# Potentiometers.net
KiCad netlist of a schematic drawn in Altium Designer
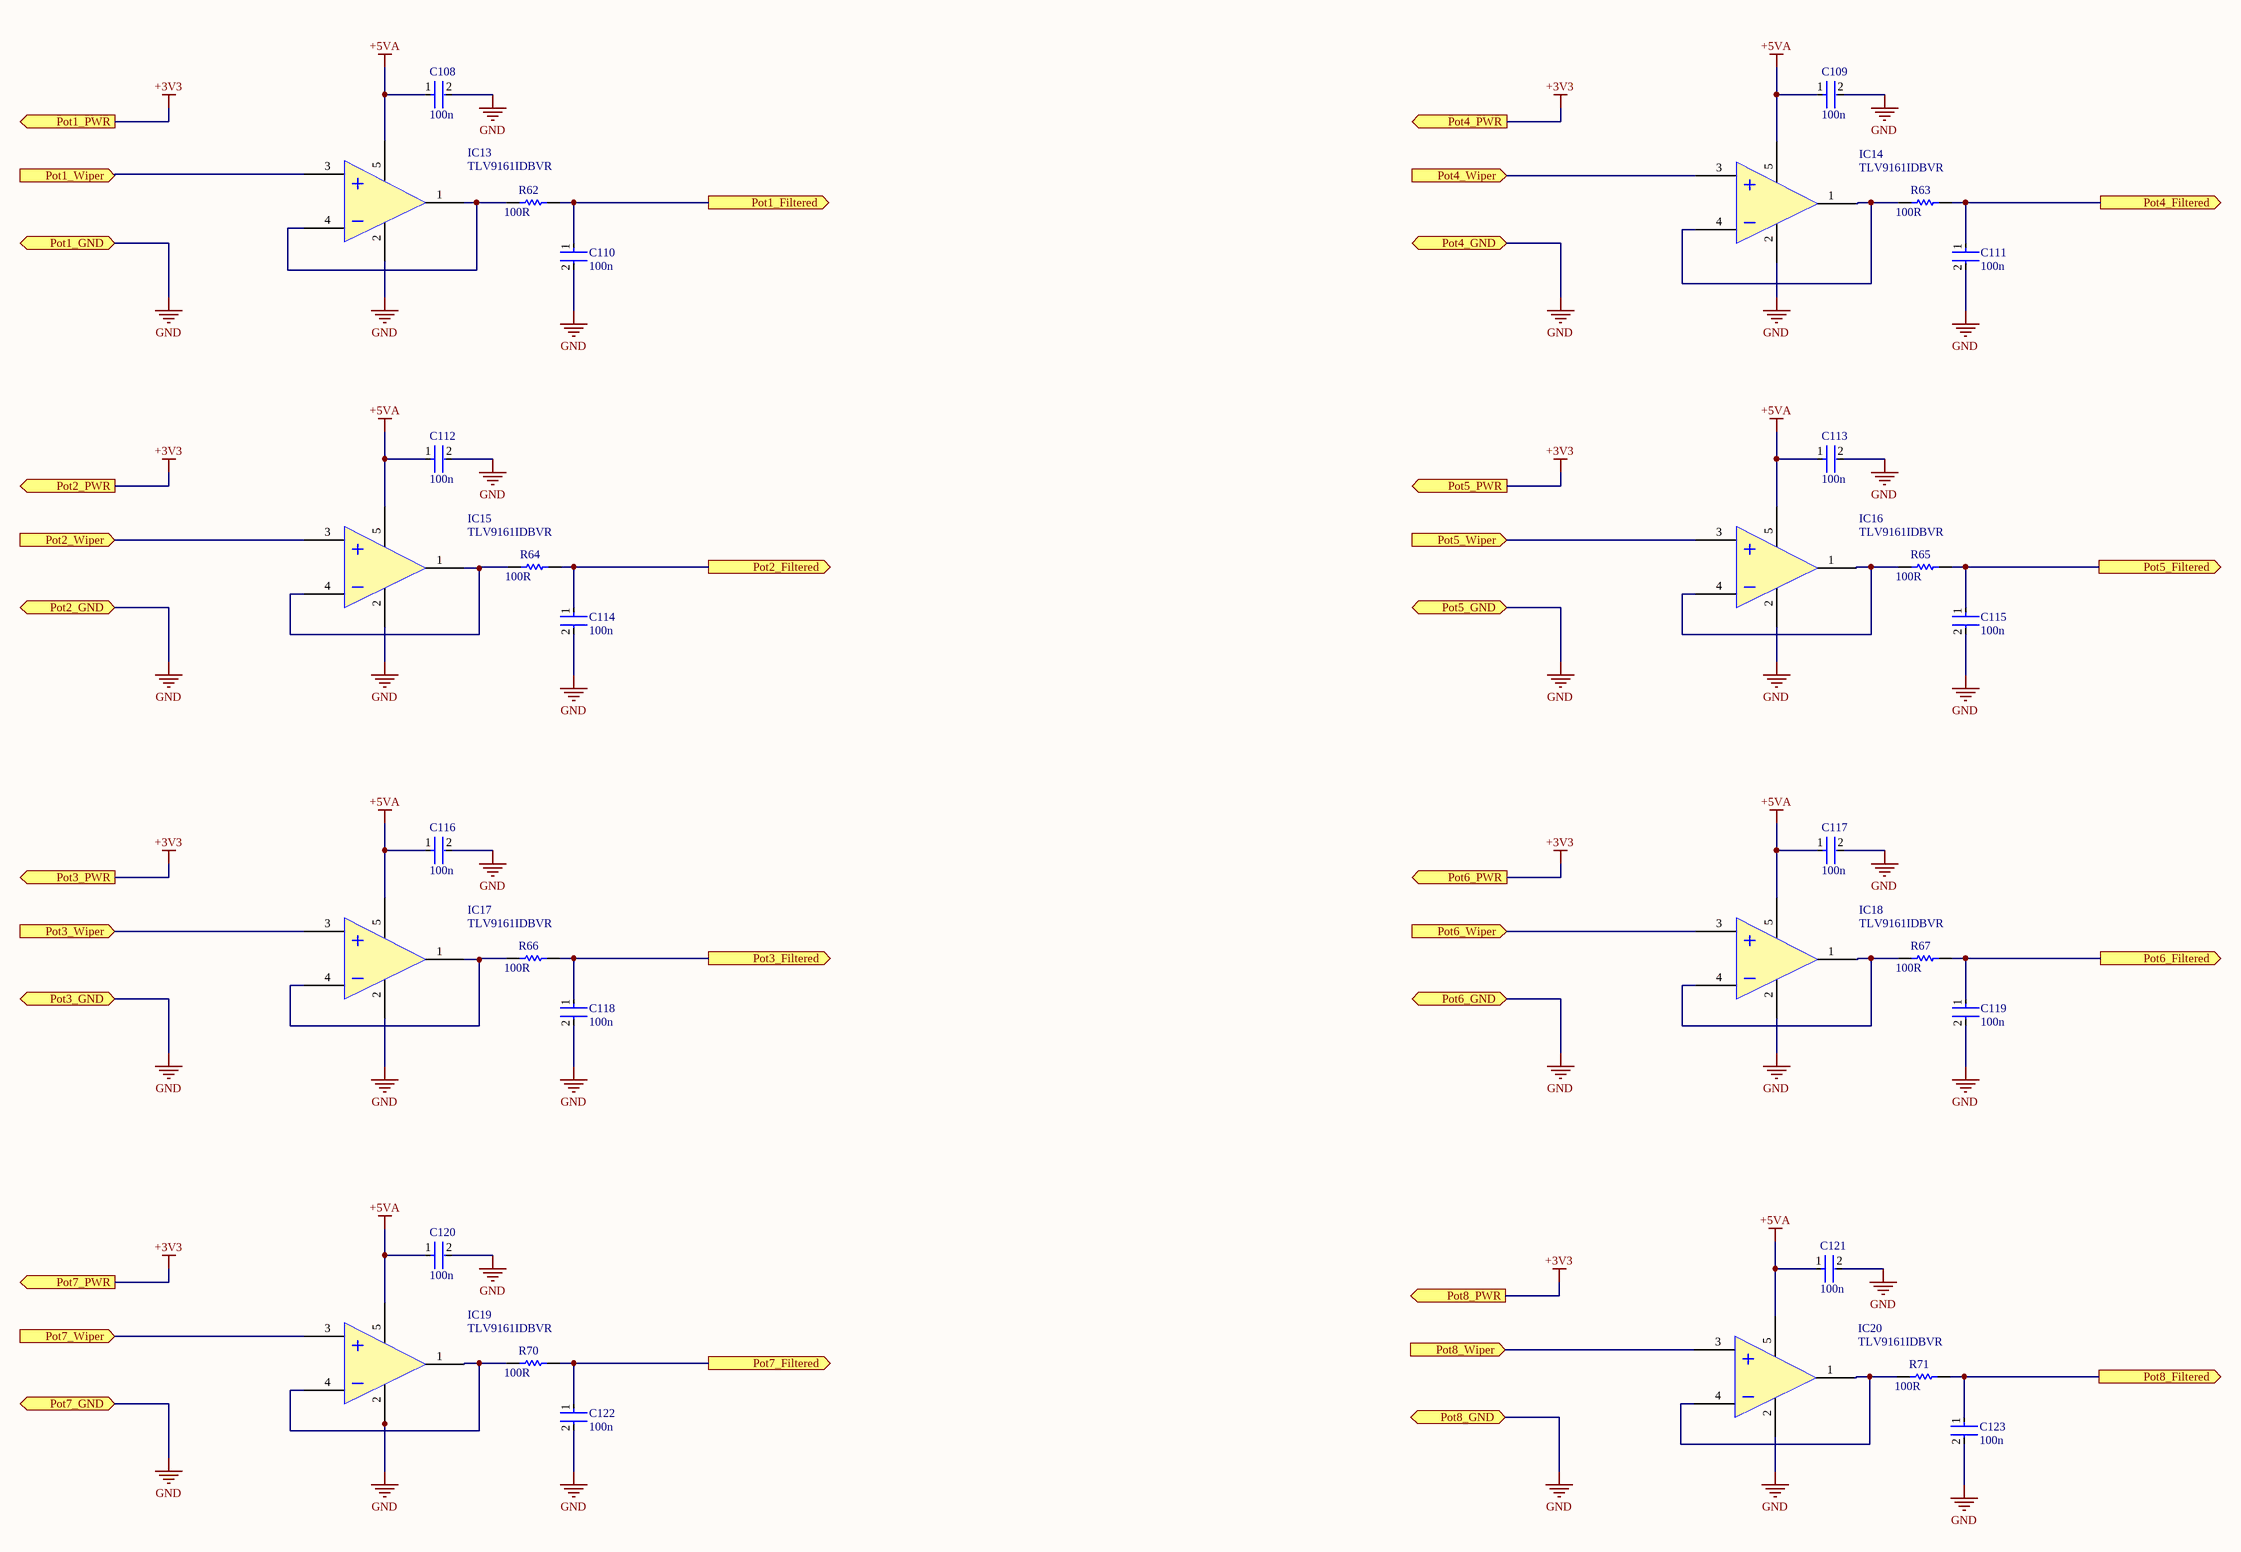
[diagram p0: Potentiometers.SchDoc]

(export (version "E")
  (design (tool "Eeschema 10.0.6"))
  (components
    (comp (ref "C108")
      (value "GCM155R71H104ME02J")
      (footprint "FP-GCM155-0_05-IPC_A")
      (description "Ceramic Capacitor for Automotive 100nF ±20% 50VDC X7R 0402 Paper T/R")
      (fields (field (name "CAPACITANCE") "100n"))
      (libsource (lib "Altium Content Vault") (part "02cd4be3c70576c341d710602a673aa"))
    )
    (comp (ref "C109")
      (value "GCM155R71H104ME02J")
      (footprint "FP-GCM155-0_05-IPC_A")
      (description "Ceramic Capacitor for Automotive 100nF ±20% 50VDC X7R 0402 Paper T/R")
      (fields (field (name "CAPACITANCE") "100n"))
      (libsource (lib "Altium Content Vault") (part "02cd4be3c70576c341d710602a673aa"))
    )
    (comp (ref "C110")
      (value "GCM155R71H104ME02J")
      (footprint "FP-GCM155-0_05-IPC_A")
      (description "Ceramic Capacitor for Automotive 100nF ±20% 50VDC X7R 0402 Paper T/R")
      (fields (field (name "CAPACITANCE") "100n"))
      (libsource (lib "Altium Content Vault") (part "02cd4be3c70576c341d710602a673aa"))
    )
    (comp (ref "C111")
      (value "GCM155R71H104ME02J")
      (footprint "FP-GCM155-0_05-IPC_A")
      (description "Ceramic Capacitor for Automotive 100nF ±20% 50VDC X7R 0402 Paper T/R")
      (fields (field (name "CAPACITANCE") "100n"))
      (libsource (lib "Altium Content Vault") (part "02cd4be3c70576c341d710602a673aa"))
    )
    (comp (ref "C112")
      (value "GCM155R71H104ME02J")
      (footprint "FP-GCM155-0_05-IPC_A")
      (description "Ceramic Capacitor for Automotive 100nF ±20% 50VDC X7R 0402 Paper T/R")
      (fields (field (name "CAPACITANCE") "100n"))
      (libsource (lib "Altium Content Vault") (part "02cd4be3c70576c341d710602a673aa"))
    )
    (comp (ref "C113")
      (value "GCM155R71H104ME02J")
      (footprint "FP-GCM155-0_05-IPC_A")
      (description "Ceramic Capacitor for Automotive 100nF ±20% 50VDC X7R 0402 Paper T/R")
      (fields (field (name "CAPACITANCE") "100n"))
      (libsource (lib "Altium Content Vault") (part "02cd4be3c70576c341d710602a673aa"))
    )
    (comp (ref "C114")
      (value "GCM155R71H104ME02J")
      (footprint "FP-GCM155-0_05-IPC_A")
      (description "Ceramic Capacitor for Automotive 100nF ±20% 50VDC X7R 0402 Paper T/R")
      (fields (field (name "CAPACITANCE") "100n"))
      (libsource (lib "Altium Content Vault") (part "02cd4be3c70576c341d710602a673aa"))
    )
    (comp (ref "C115")
      (value "GCM155R71H104ME02J")
      (footprint "FP-GCM155-0_05-IPC_A")
      (description "Ceramic Capacitor for Automotive 100nF ±20% 50VDC X7R 0402 Paper T/R")
      (fields (field (name "CAPACITANCE") "100n"))
      (libsource (lib "Altium Content Vault") (part "02cd4be3c70576c341d710602a673aa"))
    )
    (comp (ref "C116")
      (value "GCM155R71H104ME02J")
      (footprint "FP-GCM155-0_05-IPC_A")
      (description "Ceramic Capacitor for Automotive 100nF ±20% 50VDC X7R 0402 Paper T/R")
      (fields (field (name "CAPACITANCE") "100n"))
      (libsource (lib "Altium Content Vault") (part "02cd4be3c70576c341d710602a673aa"))
    )
    (comp (ref "C117")
      (value "GCM155R71H104ME02J")
      (footprint "FP-GCM155-0_05-IPC_A")
      (description "Ceramic Capacitor for Automotive 100nF ±20% 50VDC X7R 0402 Paper T/R")
      (fields (field (name "CAPACITANCE") "100n"))
      (libsource (lib "Altium Content Vault") (part "02cd4be3c70576c341d710602a673aa"))
    )
    (comp (ref "C118")
      (value "GCM155R71H104ME02J")
      (footprint "FP-GCM155-0_05-IPC_A")
      (description "Ceramic Capacitor for Automotive 100nF ±20% 50VDC X7R 0402 Paper T/R")
      (fields (field (name "CAPACITANCE") "100n"))
      (libsource (lib "Altium Content Vault") (part "02cd4be3c70576c341d710602a673aa"))
    )
    (comp (ref "C119")
      (value "GCM155R71H104ME02J")
      (footprint "FP-GCM155-0_05-IPC_A")
      (description "Ceramic Capacitor for Automotive 100nF ±20% 50VDC X7R 0402 Paper T/R")
      (fields (field (name "CAPACITANCE") "100n"))
      (libsource (lib "Altium Content Vault") (part "02cd4be3c70576c341d710602a673aa"))
    )
    (comp (ref "C120")
      (value "GCM155R71H104ME02J")
      (footprint "FP-GCM155-0_05-IPC_A")
      (description "Ceramic Capacitor for Automotive 100nF ±20% 50VDC X7R 0402 Paper T/R")
      (fields (field (name "CAPACITANCE") "100n"))
      (libsource (lib "Altium Content Vault") (part "02cd4be3c70576c341d710602a673aa"))
    )
    (comp (ref "C121")
      (value "GCM155R71H104ME02J")
      (footprint "FP-GCM155-0_05-IPC_A")
      (description "Ceramic Capacitor for Automotive 100nF ±20% 50VDC X7R 0402 Paper T/R")
      (fields (field (name "CAPACITANCE") "100n"))
      (libsource (lib "Altium Content Vault") (part "02cd4be3c70576c341d710602a673aa"))
    )
    (comp (ref "C122")
      (value "GCM155R71H104ME02J")
      (footprint "FP-GCM155-0_05-IPC_A")
      (description "Ceramic Capacitor for Automotive 100nF ±20% 50VDC X7R 0402 Paper T/R")
      (fields (field (name "CAPACITANCE") "100n"))
      (libsource (lib "Altium Content Vault") (part "02cd4be3c70576c341d710602a673aa"))
    )
    (comp (ref "C123")
      (value "GCM155R71H104ME02J")
      (footprint "FP-GCM155-0_05-IPC_A")
      (description "Ceramic Capacitor for Automotive 100nF ±20% 50VDC X7R 0402 Paper T/R")
      (fields (field (name "CAPACITANCE") "100n"))
      (libsource (lib "Altium Content Vault") (part "02cd4be3c70576c341d710602a673aa"))
    )
    (comp (ref "IC13")
      (value "TLV9161IDBVR")
      (footprint "SOT95P280X145-5N")
      (description "Integrated Circuit")
      (fields (field (name "MOUSER PART NUMBER") "595-TLV9161IDBVR"))
      (libsource (lib "audio_dev_pcb") (part "TLV9161IDBVR"))
    )
    (comp (ref "IC14")
      (value "TLV9161IDBVR")
      (footprint "SOT95P280X145-5N")
      (description "Integrated Circuit")
      (fields (field (name "MOUSER PART NUMBER") "595-TLV9161IDBVR"))
      (libsource (lib "audio_dev_pcb") (part "TLV9161IDBVR"))
    )
    (comp (ref "IC15")
      (value "TLV9161IDBVR")
      (footprint "SOT95P280X145-5N")
      (description "Integrated Circuit")
      (fields (field (name "MOUSER PART NUMBER") "595-TLV9161IDBVR"))
      (libsource (lib "audio_dev_pcb") (part "TLV9161IDBVR"))
    )
    (comp (ref "IC16")
      (value "TLV9161IDBVR")
      (footprint "SOT95P280X145-5N")
      (description "Integrated Circuit")
      (fields (field (name "MOUSER PART NUMBER") "595-TLV9161IDBVR"))
      (libsource (lib "audio_dev_pcb") (part "TLV9161IDBVR"))
    )
    (comp (ref "IC17")
      (value "TLV9161IDBVR")
      (footprint "SOT95P280X145-5N")
      (description "Integrated Circuit")
      (fields (field (name "MOUSER PART NUMBER") "595-TLV9161IDBVR"))
      (libsource (lib "audio_dev_pcb") (part "TLV9161IDBVR"))
    )
    (comp (ref "IC18")
      (value "TLV9161IDBVR")
      (footprint "SOT95P280X145-5N")
      (description "Integrated Circuit")
      (fields (field (name "MOUSER PART NUMBER") "595-TLV9161IDBVR"))
      (libsource (lib "audio_dev_pcb") (part "TLV9161IDBVR"))
    )
    (comp (ref "IC19")
      (value "TLV9161IDBVR")
      (footprint "SOT95P280X145-5N")
      (description "Integrated Circuit")
      (fields (field (name "MOUSER PART NUMBER") "595-TLV9161IDBVR"))
      (libsource (lib "audio_dev_pcb") (part "TLV9161IDBVR"))
    )
    (comp (ref "IC20")
      (value "TLV9161IDBVR")
      (footprint "SOT95P280X145-5N")
      (description "Integrated Circuit")
      (fields (field (name "MOUSER PART NUMBER") "595-TLV9161IDBVR"))
      (libsource (lib "audio_dev_pcb") (part "TLV9161IDBVR"))
    )
    (comp (ref "R62")
      (value "RC0402JR-07100RL")
      (footprint "RESC1005X40X25NL05T10")
      (fields (field (name "MANUFACTURER") "Yageo / Phycomp") (field (name "RESISTANCE") "100R"))
      (libsource (lib "Altium Content Vault") (part "RES"))
    )
    (comp (ref "R63")
      (value "RC0402JR-07100RL")
      (footprint "RESC1005X40X25NL05T10")
      (fields (field (name "MANUFACTURER") "Yageo / Phycomp") (field (name "RESISTANCE") "100R"))
      (libsource (lib "Altium Content Vault") (part "RES"))
    )
    (comp (ref "R64")
      (value "RC0402JR-07100RL")
      (footprint "RESC1005X40X25NL05T10")
      (fields (field (name "MANUFACTURER") "Yageo / Phycomp") (field (name "RESISTANCE") "100R"))
      (libsource (lib "Altium Content Vault") (part "RES"))
    )
    (comp (ref "R65")
      (value "RC0402JR-07100RL")
      (footprint "RESC1005X40X25NL05T10")
      (fields (field (name "MANUFACTURER") "Yageo / Phycomp") (field (name "RESISTANCE") "100R"))
      (libsource (lib "Altium Content Vault") (part "RES"))
    )
    (comp (ref "R66")
      (value "RC0402JR-07100RL")
      (footprint "RESC1005X40X25NL05T10")
      (fields (field (name "MANUFACTURER") "Yageo / Phycomp") (field (name "RESISTANCE") "100R"))
      (libsource (lib "Altium Content Vault") (part "RES"))
    )
    (comp (ref "R67")
      (value "RC0402JR-07100RL")
      (footprint "RESC1005X40X25NL05T10")
      (fields (field (name "MANUFACTURER") "Yageo / Phycomp") (field (name "RESISTANCE") "100R"))
      (libsource (lib "Altium Content Vault") (part "RES"))
    )
    (comp (ref "R70")
      (value "RC0402JR-07100RL")
      (footprint "RESC1005X40X25NL05T10")
      (fields (field (name "MANUFACTURER") "Yageo / Phycomp") (field (name "RESISTANCE") "100R"))
      (libsource (lib "Altium Content Vault") (part "RES"))
    )
    (comp (ref "R71")
      (value "RC0402JR-07100RL")
      (footprint "RESC1005X40X25NL05T10")
      (fields (field (name "MANUFACTURER") "Yageo / Phycomp") (field (name "RESISTANCE") "100R"))
      (libsource (lib "Altium Content Vault") (part "RES"))
    )
  )
  (nets
    (net (code "2") (name "+5VA") (class "Default")
      (node (ref "C108") (pin "1") (pinfunction "1_1") (pintype "passive"))
      (node (ref "C109") (pin "1") (pinfunction "1_1") (pintype "passive"))
      (node (ref "C112") (pin "1") (pinfunction "1_1") (pintype "passive"))
      (node (ref "C113") (pin "1") (pinfunction "1_1") (pintype "passive"))
      (node (ref "C116") (pin "1") (pinfunction "1_1") (pintype "passive"))
      (node (ref "C117") (pin "1") (pinfunction "1_1") (pintype "passive"))
      (node (ref "C120") (pin "1") (pinfunction "1_1") (pintype "passive"))
      (node (ref "C121") (pin "1") (pinfunction "1_1") (pintype "passive"))
      (node (ref "IC13") (pin "5") (pinfunction "V+_5") (pintype "passive"))
      (node (ref "IC14") (pin "5") (pinfunction "V+_5") (pintype "passive"))
      (node (ref "IC15") (pin "5") (pinfunction "V+_5") (pintype "passive"))
      (node (ref "IC16") (pin "5") (pinfunction "V+_5") (pintype "passive"))
      (node (ref "IC17") (pin "5") (pinfunction "V+_5") (pintype "passive"))
      (node (ref "IC18") (pin "5") (pinfunction "V+_5") (pintype "passive"))
      (node (ref "IC19") (pin "5") (pinfunction "V+_5") (pintype "passive"))
      (node (ref "IC20") (pin "5") (pinfunction "V+_5") (pintype "passive"))
    )
    (net (code "3") (name "/Pot1_Filtered") (class "Default")
      (node (ref "C110") (pin "1") (pinfunction "1_1") (pintype "passive"))
      (node (ref "R62") (pin "2") (pinfunction "2_2") (pintype "passive"))
    )
    (net (code "4") (name "/Pot1_Wiper") (class "Default")
      (node (ref "IC13") (pin "3") (pinfunction "IN+_3") (pintype "passive"))
    )
    (net (code "5") (name "/Pot2_Filtered") (class "Default")
      (node (ref "C114") (pin "1") (pinfunction "1_1") (pintype "passive"))
      (node (ref "R64") (pin "2") (pinfunction "2_2") (pintype "passive"))
    )
    (net (code "6") (name "/Pot2_Wiper") (class "Default")
      (node (ref "IC15") (pin "3") (pinfunction "IN+_3") (pintype "passive"))
    )
    (net (code "7") (name "/Pot3_Filtered") (class "Default")
      (node (ref "C118") (pin "1") (pinfunction "1_1") (pintype "passive"))
      (node (ref "R66") (pin "2") (pinfunction "2_2") (pintype "passive"))
    )
    (net (code "8") (name "/Pot3_Wiper") (class "Default")
      (node (ref "IC17") (pin "3") (pinfunction "IN+_3") (pintype "passive"))
    )
    (net (code "9") (name "/Pot4_Filtered") (class "Default")
      (node (ref "C111") (pin "1") (pinfunction "1_1") (pintype "passive"))
      (node (ref "R63") (pin "2") (pinfunction "2_2") (pintype "passive"))
    )
    (net (code "10") (name "/Pot4_Wiper") (class "Default")
      (node (ref "IC14") (pin "3") (pinfunction "IN+_3") (pintype "passive"))
    )
    (net (code "11") (name "/Pot5_Filtered") (class "Default")
      (node (ref "C115") (pin "1") (pinfunction "1_1") (pintype "passive"))
      (node (ref "R65") (pin "2") (pinfunction "2_2") (pintype "passive"))
    )
    (net (code "12") (name "/Pot5_Wiper") (class "Default")
      (node (ref "IC16") (pin "3") (pinfunction "IN+_3") (pintype "passive"))
    )
    (net (code "13") (name "/Pot6_Filtered") (class "Default")
      (node (ref "C119") (pin "1") (pinfunction "1_1") (pintype "passive"))
      (node (ref "R67") (pin "2") (pinfunction "2_2") (pintype "passive"))
    )
    (net (code "14") (name "/Pot6_Wiper") (class "Default")
      (node (ref "IC18") (pin "3") (pinfunction "IN+_3") (pintype "passive"))
    )
    (net (code "15") (name "/Pot7_Filtered") (class "Default")
      (node (ref "C122") (pin "1") (pinfunction "1_1") (pintype "passive"))
      (node (ref "R70") (pin "2") (pinfunction "2_2") (pintype "passive"))
    )
    (net (code "16") (name "/Pot7_Wiper") (class "Default")
      (node (ref "IC19") (pin "3") (pinfunction "IN+_3") (pintype "passive"))
    )
    (net (code "17") (name "/Pot8_Filtered") (class "Default")
      (node (ref "C123") (pin "1") (pinfunction "1_1") (pintype "passive"))
      (node (ref "R71") (pin "2") (pinfunction "2_2") (pintype "passive"))
    )
    (net (code "18") (name "/Pot8_Wiper") (class "Default")
      (node (ref "IC20") (pin "3") (pinfunction "IN+_3") (pintype "passive"))
    )
    (net (code "19") (name "GND") (class "Default")
      (node (ref "C108") (pin "2") (pinfunction "2_2") (pintype "passive"))
      (node (ref "C109") (pin "2") (pinfunction "2_2") (pintype "passive"))
      (node (ref "C110") (pin "2") (pinfunction "2_2") (pintype "passive"))
      (node (ref "C111") (pin "2") (pinfunction "2_2") (pintype "passive"))
      (node (ref "C112") (pin "2") (pinfunction "2_2") (pintype "passive"))
      (node (ref "C113") (pin "2") (pinfunction "2_2") (pintype "passive"))
      (node (ref "C114") (pin "2") (pinfunction "2_2") (pintype "passive"))
      (node (ref "C115") (pin "2") (pinfunction "2_2") (pintype "passive"))
      (node (ref "C116") (pin "2") (pinfunction "2_2") (pintype "passive"))
      (node (ref "C117") (pin "2") (pinfunction "2_2") (pintype "passive"))
      (node (ref "C118") (pin "2") (pinfunction "2_2") (pintype "passive"))
      (node (ref "C119") (pin "2") (pinfunction "2_2") (pintype "passive"))
      (node (ref "C120") (pin "2") (pinfunction "2_2") (pintype "passive"))
      (node (ref "C121") (pin "2") (pinfunction "2_2") (pintype "passive"))
      (node (ref "C122") (pin "2") (pinfunction "2_2") (pintype "passive"))
      (node (ref "C123") (pin "2") (pinfunction "2_2") (pintype "passive"))
      (node (ref "IC13") (pin "2") (pinfunction "V-_2") (pintype "passive"))
      (node (ref "IC14") (pin "2") (pinfunction "V-_2") (pintype "passive"))
      (node (ref "IC15") (pin "2") (pinfunction "V-_2") (pintype "passive"))
      (node (ref "IC16") (pin "2") (pinfunction "V-_2") (pintype "passive"))
      (node (ref "IC17") (pin "2") (pinfunction "V-_2") (pintype "passive"))
      (node (ref "IC18") (pin "2") (pinfunction "V-_2") (pintype "passive"))
      (node (ref "IC19") (pin "2") (pinfunction "V-_2") (pintype "passive"))
      (node (ref "IC20") (pin "2") (pinfunction "V-_2") (pintype "passive"))
    )
    (net (code "20") (name "Net-(IC13-IN-)") (class "Default")
      (node (ref "IC13") (pin "1") (pinfunction "OUT_1") (pintype "passive"))
      (node (ref "IC13") (pin "4") (pinfunction "IN-_4") (pintype "passive"))
      (node (ref "R62") (pin "1") (pinfunction "1_1") (pintype "passive"))
    )
    (net (code "21") (name "Net-(IC14-IN-)") (class "Default")
      (node (ref "IC14") (pin "1") (pinfunction "OUT_1") (pintype "passive"))
      (node (ref "IC14") (pin "4") (pinfunction "IN-_4") (pintype "passive"))
      (node (ref "R63") (pin "1") (pinfunction "1_1") (pintype "passive"))
    )
    (net (code "22") (name "Net-(IC15-IN-)") (class "Default")
      (node (ref "IC15") (pin "1") (pinfunction "OUT_1") (pintype "passive"))
      (node (ref "IC15") (pin "4") (pinfunction "IN-_4") (pintype "passive"))
      (node (ref "R64") (pin "1") (pinfunction "1_1") (pintype "passive"))
    )
    (net (code "23") (name "Net-(IC16-IN-)") (class "Default")
      (node (ref "IC16") (pin "1") (pinfunction "OUT_1") (pintype "passive"))
      (node (ref "IC16") (pin "4") (pinfunction "IN-_4") (pintype "passive"))
      (node (ref "R65") (pin "1") (pinfunction "1_1") (pintype "passive"))
    )
    (net (code "24") (name "Net-(IC17-IN-)") (class "Default")
      (node (ref "IC17") (pin "1") (pinfunction "OUT_1") (pintype "passive"))
      (node (ref "IC17") (pin "4") (pinfunction "IN-_4") (pintype "passive"))
      (node (ref "R66") (pin "1") (pinfunction "1_1") (pintype "passive"))
    )
    (net (code "25") (name "Net-(IC18-IN-)") (class "Default")
      (node (ref "IC18") (pin "1") (pinfunction "OUT_1") (pintype "passive"))
      (node (ref "IC18") (pin "4") (pinfunction "IN-_4") (pintype "passive"))
      (node (ref "R67") (pin "1") (pinfunction "1_1") (pintype "passive"))
    )
    (net (code "26") (name "Net-(IC19-IN-)") (class "Default")
      (node (ref "IC19") (pin "1") (pinfunction "OUT_1") (pintype "passive"))
      (node (ref "IC19") (pin "4") (pinfunction "IN-_4") (pintype "passive"))
      (node (ref "R70") (pin "1") (pinfunction "1_1") (pintype "passive"))
    )
    (net (code "27") (name "Net-(IC20-IN-)") (class "Default")
      (node (ref "IC20") (pin "1") (pinfunction "OUT_1") (pintype "passive"))
      (node (ref "IC20") (pin "4") (pinfunction "IN-_4") (pintype "passive"))
      (node (ref "R71") (pin "1") (pinfunction "1_1") (pintype "passive"))
    )
  )
)
